# amplifier.net
KiCad netlist of a schematic drawn in EAGLE
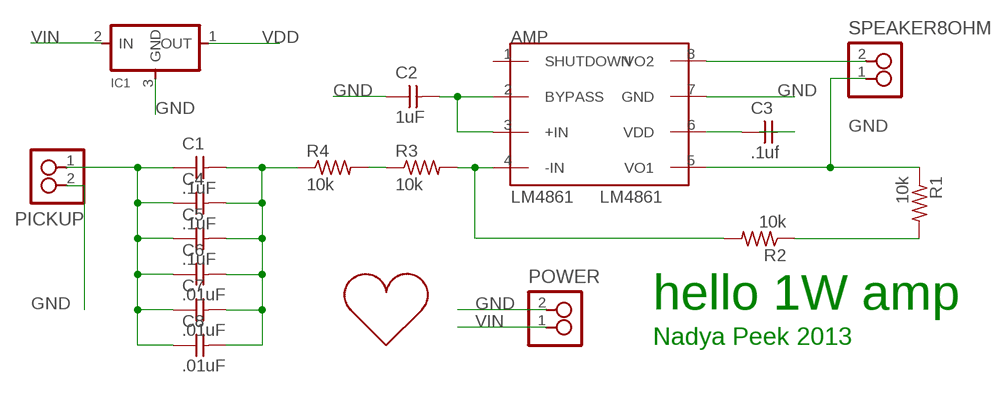
[diagram p0: schematic, sheet 1]

(export (version "E")
  (design (tool "Eeschema 10.0.6"))
  (components
    (comp (ref "AMP")
      (value "LM4861")
      (footprint "eagle-import:SOIC8")
      (libsource (lib "eagle-import") (part "LM4861"))
    )
    (comp (ref "C1")
      (value ".1uF")
      (footprint "eagle-import:1206")
      (libsource (lib "eagle-import") (part "UNPOLARIZED_CAPACITOR1206"))
    )
    (comp (ref "C2")
      (value "1uF")
      (footprint "eagle-import:1206")
      (libsource (lib "eagle-import") (part "UNPOLARIZED_CAPACITOR1206"))
    )
    (comp (ref "C3")
      (value ".1uf")
      (footprint "eagle-import:1206")
      (libsource (lib "eagle-import") (part "UNPOLARIZED_CAPACITOR1206"))
    )
    (comp (ref "C4")
      (value ".1uF")
      (footprint "eagle-import:1206")
      (libsource (lib "eagle-import") (part "UNPOLARIZED_CAPACITOR1206"))
    )
    (comp (ref "C5")
      (value ".1uF")
      (footprint "eagle-import:1206")
      (libsource (lib "eagle-import") (part "UNPOLARIZED_CAPACITOR1206"))
    )
    (comp (ref "C6")
      (value ".01uF")
      (footprint "eagle-import:1206")
      (libsource (lib "eagle-import") (part "UNPOLARIZED_CAPACITOR1206"))
    )
    (comp (ref "C7")
      (value ".01uF")
      (footprint "eagle-import:1206")
      (libsource (lib "eagle-import") (part "UNPOLARIZED_CAPACITOR1206"))
    )
    (comp (ref "C8")
      (value ".01uF")
      (footprint "eagle-import:1206")
      (libsource (lib "eagle-import") (part "UNPOLARIZED_CAPACITOR1206"))
    )
    (comp (ref "IC1")
      (value "REGULATORSOT23")
      (footprint "eagle-import:SOT23")
      (libsource (lib "eagle-import") (part "REGULATORSOT23"))
    )
    (comp (ref "PICKUP")
      (value "2_PIN_HEADERSCREW")
      (footprint "eagle-import:SCREW_2")
      (libsource (lib "eagle-import") (part "2_PIN_HEADERSCREW"))
    )
    (comp (ref "POWER")
      (value "2_PIN_HEADERSCREW")
      (footprint "eagle-import:SCREW_2")
      (libsource (lib "eagle-import") (part "2_PIN_HEADERSCREW"))
    )
    (comp (ref "R1")
      (value "10k")
      (footprint "eagle-import:1206")
      (libsource (lib "eagle-import") (part "RESISTOR1206"))
    )
    (comp (ref "R2")
      (value "10k")
      (footprint "eagle-import:1206")
      (libsource (lib "eagle-import") (part "RESISTOR1206"))
    )
    (comp (ref "R3")
      (value "10k")
      (footprint "eagle-import:1206")
      (libsource (lib "eagle-import") (part "RESISTOR1206"))
    )
    (comp (ref "R4")
      (value "10k")
      (footprint "eagle-import:1206")
      (libsource (lib "eagle-import") (part "RESISTOR1206"))
    )
    (comp (ref "SPEAKER8OHM")
      (value "2_PIN_HEADERSCREW")
      (footprint "eagle-import:SCREW_2")
      (libsource (lib "eagle-import") (part "2_PIN_HEADERSCREW"))
    )
    (comp (ref "U$2")
      (value "SMALLHEARTSMALL")
      (footprint "eagle-import:SMALLERHEART")
      (libsource (lib "eagle-import") (part "SMALLHEARTSMALL"))
    )
  )
  (nets
    (net (code "1") (name "/GND") (class "Default")
      (node (ref "AMP") (pin "7") (pinfunction "GND_7") (pintype "bidirectional"))
      (node (ref "C2") (pin "1") (pinfunction "1_1") (pintype "passive"))
      (node (ref "C3") (pin "2") (pinfunction "2_2") (pintype "passive"))
      (node (ref "IC1") (pin "3") (pinfunction "GND_3") (pintype "bidirectional"))
      (node (ref "PICKUP") (pin "2") (pinfunction "2_2") (pintype "bidirectional"))
      (node (ref "POWER") (pin "2") (pinfunction "2_2") (pintype "bidirectional"))
    )
    (net (code "2") (name "/VDD") (class "Default")
      (node (ref "AMP") (pin "6") (pinfunction "VDD_6") (pintype "bidirectional"))
      (node (ref "C3") (pin "1") (pinfunction "1_1") (pintype "passive"))
      (node (ref "IC1") (pin "1") (pinfunction "OUT_1") (pintype "bidirectional"))
    )
    (net (code "3") (name "/VIN") (class "Default")
      (node (ref "IC1") (pin "2") (pinfunction "IN_2") (pintype "bidirectional"))
      (node (ref "POWER") (pin "1") (pinfunction "1_1") (pintype "bidirectional"))
    )
    (net (code "4") (name "Net-(AMP-+IN)") (class "Default")
      (node (ref "AMP") (pin "2") (pinfunction "BYPASS_2") (pintype "bidirectional"))
      (node (ref "AMP") (pin "3") (pinfunction "+IN_3") (pintype "bidirectional"))
      (node (ref "C2") (pin "2") (pinfunction "2_2") (pintype "passive"))
    )
    (net (code "5") (name "Net-(AMP--IN)") (class "Default")
      (node (ref "AMP") (pin "4") (pinfunction "-IN_4") (pintype "bidirectional"))
      (node (ref "R2") (pin "2") (pinfunction "2_2") (pintype "passive"))
      (node (ref "R3") (pin "2") (pinfunction "2_2") (pintype "passive"))
    )
    (net (code "6") (name "Net-(AMP-VO1)") (class "Default")
      (node (ref "AMP") (pin "5") (pinfunction "VO1_5") (pintype "bidirectional"))
      (node (ref "R1") (pin "1") (pinfunction "1_1") (pintype "passive"))
      (node (ref "SPEAKER8OHM") (pin "1") (pinfunction "1_1") (pintype "bidirectional"))
    )
    (net (code "7") (name "Net-(AMP-VO2)") (class "Default")
      (node (ref "AMP") (pin "8") (pinfunction "VO2_8") (pintype "bidirectional"))
      (node (ref "SPEAKER8OHM") (pin "2") (pinfunction "2_2") (pintype "bidirectional"))
    )
    (net (code "8") (name "Net-(C1-Pad1)") (class "Default")
      (node (ref "C1") (pin "1") (pinfunction "1_1") (pintype "passive"))
      (node (ref "C4") (pin "1") (pinfunction "1_1") (pintype "passive"))
      (node (ref "C5") (pin "1") (pinfunction "1_1") (pintype "passive"))
      (node (ref "C6") (pin "1") (pinfunction "1_1") (pintype "passive"))
      (node (ref "C7") (pin "1") (pinfunction "1_1") (pintype "passive"))
      (node (ref "C8") (pin "1") (pinfunction "1_1") (pintype "passive"))
      (node (ref "PICKUP") (pin "1") (pinfunction "1_1") (pintype "bidirectional"))
    )
    (net (code "9") (name "Net-(C1-Pad2)") (class "Default")
      (node (ref "C1") (pin "2") (pinfunction "2_2") (pintype "passive"))
      (node (ref "C4") (pin "2") (pinfunction "2_2") (pintype "passive"))
      (node (ref "C5") (pin "2") (pinfunction "2_2") (pintype "passive"))
      (node (ref "C6") (pin "2") (pinfunction "2_2") (pintype "passive"))
      (node (ref "C7") (pin "2") (pinfunction "2_2") (pintype "passive"))
      (node (ref "C8") (pin "2") (pinfunction "2_2") (pintype "passive"))
      (node (ref "R4") (pin "1") (pinfunction "1_1") (pintype "passive"))
    )
    (net (code "10") (name "Net-(R1-Pad2)") (class "Default")
      (node (ref "R1") (pin "2") (pinfunction "2_2") (pintype "passive"))
      (node (ref "R2") (pin "1") (pinfunction "1_1") (pintype "passive"))
    )
    (net (code "11") (name "Net-(R3-Pad1)") (class "Default")
      (node (ref "R3") (pin "1") (pinfunction "1_1") (pintype "passive"))
      (node (ref "R4") (pin "2") (pinfunction "2_2") (pintype "passive"))
    )
    (net (code "12") (name "unconnected-(AMP-SHUTDOWN-Pad1)") (class "Default")
      (node (ref "AMP") (pin "1") (pinfunction "SHUTDOWN_1") (pintype "bidirectional"))
    )
  )
)
